# MIC5317.net
KiCad netlist of a schematic drawn in Altium Designer
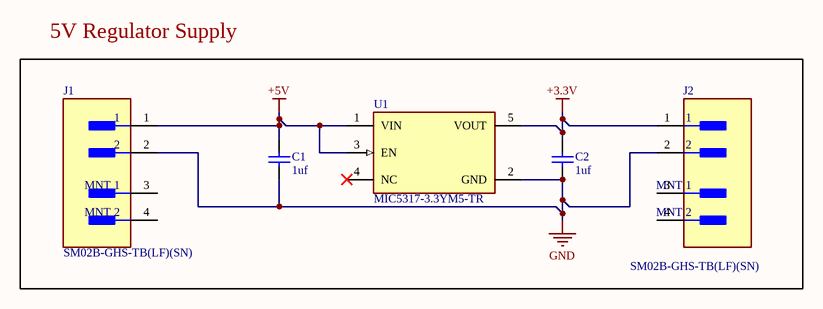
[diagram p0: MIC5317.SchDoc]

(export (version "E")
  (design (tool "Eeschema 10.0.6"))
  (components
    (comp (ref "C1")
      (value "1uf")
      (footprint "CAPC2013X140X50LL20T25")
      (fields (field (name "PART NUMBER") "C0805C105K3RACTU") (field (name "MANUFACTURER") "Kemet"))
      (libsource (lib "Altium Content Vault") (part "CAP"))
    )
    (comp (ref "C2")
      (value "1uf")
      (footprint "CAPC2013X140X50LL20T25")
      (fields (field (name "PART NUMBER") "C0805C105K3RACTU") (field (name "MANUFACTURER") "Kemet"))
      (libsource (lib "Altium Content Vault") (part "CAP"))
    )
    (comp (ref "J1")
      (value "SM02B-GHS-TB(LF)(SN)")
      (footprint "FP-SM02B-GHS-TB_LF_SN-MFG")
      (description "CONN HEADER SMD R/A 2POS 1.25MM")
      (libsource (lib "Altium Content Vault") (part "56ec3178a87b3978bdc1b3682cd516a"))
    )
    (comp (ref "J2")
      (value "SM02B-GHS-TB(LF)(SN)")
      (footprint "FP-SM02B-GHS-TB_LF_SN-MFG")
      (description "CONN HEADER SMD R/A 2POS 1.25MM")
      (libsource (lib "") (part "56ec3178a87b3978bdc1b3682cd516a_1"))
    )
    (comp (ref "U1")
      (value "MIC5317-3.3YM5-TR")
      (footprint "FP-SOT23-5LD-PL-1-MFG")
      (description "IC REG LINEAR 3.3V 150MA SOT23-5")
      (libsource (lib "Altium Content Vault") (part "0a093dae7315cdc977fd108dde87457"))
    )
  )
  (nets
    (net (code "1") (name "+3.3V") (class "Default")
      (node (ref "C2") (pin "1") (pinfunction "1_1") (pintype "passive"))
      (node (ref "J2") (pin "1") (pinfunction "1_1") (pintype "passive"))
      (node (ref "U1") (pin "5") (pinfunction "VOUT_5") (pintype "power_in"))
    )
    (net (code "2") (name "+5V") (class "Default")
      (node (ref "C1") (pin "2") (pinfunction "2_2") (pintype "passive"))
      (node (ref "J1") (pin "1") (pinfunction "1_1") (pintype "passive"))
      (node (ref "U1") (pin "1") (pinfunction "VIN_1") (pintype "power_in"))
      (node (ref "U1") (pin "3") (pinfunction "EN_3") (pintype "input"))
    )
    (net (code "3") (name "GND") (class "Default")
      (node (ref "C1") (pin "1") (pinfunction "1_1") (pintype "passive"))
      (node (ref "C2") (pin "2") (pinfunction "2_2") (pintype "passive"))
      (node (ref "J1") (pin "2") (pinfunction "2_2") (pintype "passive"))
      (node (ref "J2") (pin "2") (pinfunction "2_2") (pintype "passive"))
      (node (ref "U1") (pin "2") (pinfunction "GND_2") (pintype "power_in"))
    )
    (net (code "4") (name "unconnected-(J1-MNT_1-Pad3)") (class "Default")
      (node (ref "J1") (pin "3") (pinfunction "MNT_1_3") (pintype "passive"))
    )
    (net (code "5") (name "unconnected-(J1-MNT_2-Pad4)") (class "Default")
      (node (ref "J1") (pin "4") (pinfunction "MNT_2_4") (pintype "passive"))
    )
    (net (code "6") (name "unconnected-(J2-MNT_1-Pad3)") (class "Default")
      (node (ref "J2") (pin "3") (pinfunction "MNT_1_3") (pintype "passive"))
    )
    (net (code "7") (name "unconnected-(J2-MNT_2-Pad4)") (class "Default")
      (node (ref "J2") (pin "4") (pinfunction "MNT_2_4") (pintype "passive"))
    )
    (net (code "8") (name "unconnected-(U1-NC-Pad4)") (class "Default")
      (node (ref "U1") (pin "4") (pinfunction "NC_4") (pintype "passive+no_connect"))
    )
  )
)
